# Inputs.net
KiCad netlist of a schematic drawn in Altium Designer
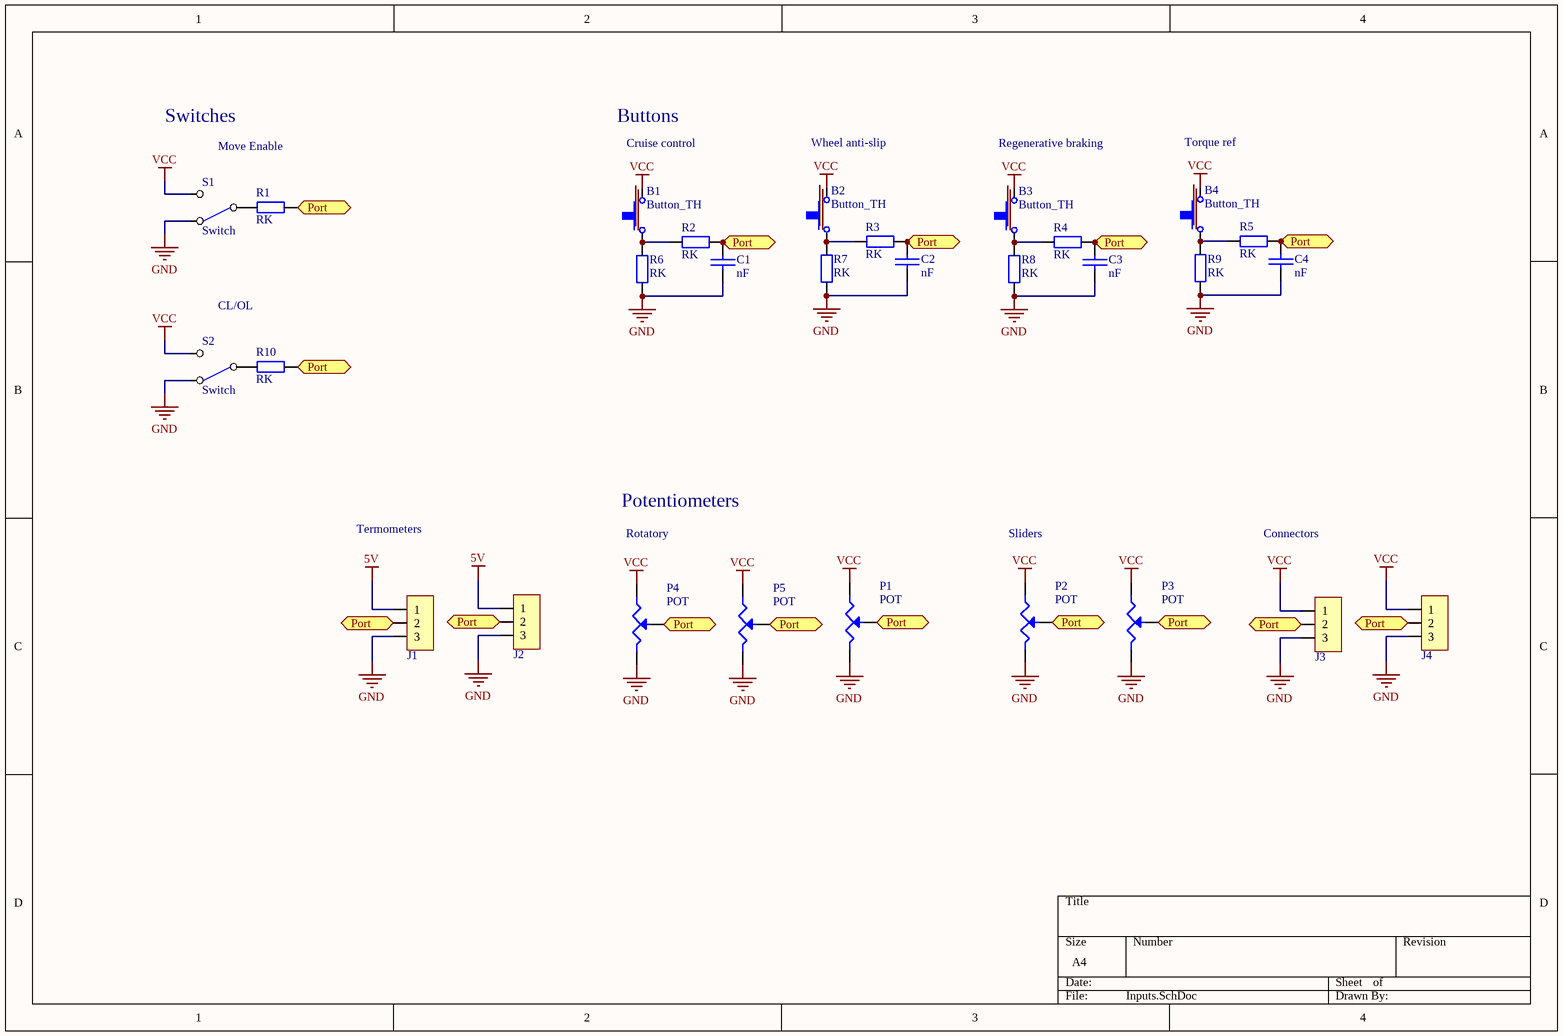
[diagram p0: Inputs.SchDoc]

(export (version "E")
  (design (tool "Eeschema 10.0.6"))
  (components
    (comp (ref "B1")
      (value "Button_TH")
      (footprint "ButtonTH")
      (libsource (lib "SCH_Lib") (part "Button_TH"))
    )
    (comp (ref "B2")
      (value "Button_TH")
      (footprint "ButtonTH")
      (libsource (lib "SCH_Lib") (part "Button_TH"))
    )
    (comp (ref "B3")
      (value "Button_TH")
      (footprint "ButtonTH")
      (libsource (lib "SCH_Lib") (part "Button_TH"))
    )
    (comp (ref "B4")
      (value "Button_TH")
      (footprint "ButtonTH")
      (libsource (lib "SCH_Lib") (part "Button_TH"))
    )
    (comp (ref "C1")
      (value "nF")
      (footprint "1206")
      (description "Condensador")
      (libsource (lib "SCH_Lib") (part "Condensador"))
    )
    (comp (ref "C2")
      (value "nF")
      (footprint "1206")
      (description "Condensador")
      (libsource (lib "SCH_Lib") (part "Condensador"))
    )
    (comp (ref "C3")
      (value "nF")
      (footprint "1206")
      (description "Condensador")
      (libsource (lib "SCH_Lib") (part "Condensador"))
    )
    (comp (ref "C4")
      (value "nF")
      (footprint "1206")
      (description "Condensador")
      (libsource (lib "SCH_Lib") (part "Condensador"))
    )
    (comp (ref "J1")
      (value "Cleva 2 vias")
      (footprint "Con3_KK_256")
      (libsource (lib "SCH_Lib") (part "Con_3"))
    )
    (comp (ref "J2")
      (value "Cleva 2 vias")
      (footprint "Con3_KK_256")
      (libsource (lib "SCH_Lib") (part "Con_3"))
    )
    (comp (ref "J3")
      (value "Cleva 2 vias")
      (footprint "Con3_KK_256")
      (libsource (lib "SCH_Lib") (part "Con_3"))
    )
    (comp (ref "J4")
      (value "Cleva 2 vias")
      (footprint "Con3_KK_256")
      (libsource (lib "SCH_Lib") (part "Con_3"))
    )
    (comp (ref "P1")
      (value "POT")
      (footprint "POT_RK11K1140A3L")
      (description "POTENCIOMETRO")
      (libsource (lib "SCH_Lib") (part "POT"))
    )
    (comp (ref "P2")
      (value "POT")
      (footprint "SliderPot_PTA6044")
      (description "POTENCIOMETRO")
      (libsource (lib "SCH_Lib") (part "POT"))
    )
    (comp (ref "P3")
      (value "POT")
      (footprint "SliderPot_PTA6044")
      (description "POTENCIOMETRO")
      (libsource (lib "SCH_Lib") (part "POT"))
    )
    (comp (ref "P4")
      (value "POT")
      (footprint "POT_RK11K1140A3L")
      (description "POTENCIOMETRO")
      (libsource (lib "SCH_Lib") (part "POT"))
    )
    (comp (ref "P5")
      (value "POT")
      (footprint "POT_RK11K1140A3L")
      (description "POTENCIOMETRO")
      (libsource (lib "SCH_Lib") (part "POT"))
    )
    (comp (ref "R1")
      (value "RK")
      (footprint "1206")
      (description "Resistencia")
      (libsource (lib "SCH_Lib") (part "Resistencia"))
    )
    (comp (ref "R2")
      (value "RK")
      (footprint "1206")
      (description "Resistencia")
      (libsource (lib "SCH_Lib") (part "Resistencia"))
    )
    (comp (ref "R3")
      (value "RK")
      (footprint "1206")
      (description "Resistencia")
      (libsource (lib "SCH_Lib") (part "Resistencia"))
    )
    (comp (ref "R4")
      (value "RK")
      (footprint "1206")
      (description "Resistencia")
      (libsource (lib "SCH_Lib") (part "Resistencia"))
    )
    (comp (ref "R5")
      (value "RK")
      (footprint "1206")
      (description "Resistencia")
      (libsource (lib "SCH_Lib") (part "Resistencia"))
    )
    (comp (ref "R6")
      (value "RK")
      (footprint "1206")
      (description "Resistencia")
      (libsource (lib "SCH_Lib") (part "Resistencia"))
    )
    (comp (ref "R7")
      (value "RK")
      (footprint "1206")
      (description "Resistencia")
      (libsource (lib "SCH_Lib") (part "Resistencia"))
    )
    (comp (ref "R8")
      (value "RK")
      (footprint "1206")
      (description "Resistencia")
      (libsource (lib "SCH_Lib") (part "Resistencia"))
    )
    (comp (ref "R9")
      (value "RK")
      (footprint "1206")
      (description "Resistencia")
      (libsource (lib "SCH_Lib") (part "Resistencia"))
    )
    (comp (ref "R10")
      (value "RK")
      (footprint "1206")
      (description "Resistencia")
      (libsource (lib "SCH_Lib") (part "Resistencia"))
    )
    (comp (ref "S1") (value "Switch") (footprint "SwitchTH_2Pos") (libsource (lib "SCH_Lib") (part "Switch")))
    (comp (ref "S2") (value "Switch") (footprint "SwitchTH_2Pos") (libsource (lib "SCH_Lib") (part "Switch")))
  )
  (nets
    (net (code "1") (name "/Port") (class "Default")
      (node (ref "C1") (pin "1") (pintype "passive"))
      (node (ref "C2") (pin "1") (pintype "passive"))
      (node (ref "C3") (pin "1") (pintype "passive"))
      (node (ref "C4") (pin "1") (pintype "passive"))
      (node (ref "J1") (pin "2") (pinfunction "2_2") (pintype "passive"))
      (node (ref "J2") (pin "2") (pinfunction "2_2") (pintype "passive"))
      (node (ref "J3") (pin "2") (pinfunction "2_2") (pintype "passive"))
      (node (ref "J4") (pin "2") (pinfunction "2_2") (pintype "passive"))
      (node (ref "P1") (pin "2") (pinfunction "2_2") (pintype "passive"))
      (node (ref "P2") (pin "2") (pinfunction "2_2") (pintype "passive"))
      (node (ref "P3") (pin "2") (pinfunction "2_2") (pintype "passive"))
      (node (ref "P4") (pin "2") (pinfunction "2_2") (pintype "passive"))
      (node (ref "P5") (pin "2") (pinfunction "2_2") (pintype "passive"))
      (node (ref "R1") (pin "2") (pinfunction "2_2") (pintype "passive"))
      (node (ref "R10") (pin "2") (pinfunction "2_2") (pintype "passive"))
      (node (ref "R2") (pin "1") (pinfunction "1_1") (pintype "passive"))
      (node (ref "R3") (pin "1") (pinfunction "1_1") (pintype "passive"))
      (node (ref "R4") (pin "1") (pinfunction "1_1") (pintype "passive"))
      (node (ref "R5") (pin "1") (pinfunction "1_1") (pintype "passive"))
    )
    (net (code "2") (name "5V") (class "Default")
      (node (ref "J1") (pin "1") (pinfunction "1_1") (pintype "passive"))
      (node (ref "J2") (pin "1") (pinfunction "1_1") (pintype "passive"))
    )
    (net (code "3") (name "GND") (class "Default")
      (node (ref "C1") (pin "2") (pintype "passive"))
      (node (ref "C2") (pin "2") (pintype "passive"))
      (node (ref "C3") (pin "2") (pintype "passive"))
      (node (ref "C4") (pin "2") (pintype "passive"))
      (node (ref "J1") (pin "3") (pinfunction "3_3") (pintype "passive"))
      (node (ref "J2") (pin "3") (pinfunction "3_3") (pintype "passive"))
      (node (ref "J3") (pin "3") (pinfunction "3_3") (pintype "passive"))
      (node (ref "J4") (pin "3") (pinfunction "3_3") (pintype "passive"))
      (node (ref "P1") (pin "3") (pinfunction "3_3") (pintype "passive"))
      (node (ref "P2") (pin "3") (pinfunction "3_3") (pintype "passive"))
      (node (ref "P3") (pin "3") (pinfunction "3_3") (pintype "passive"))
      (node (ref "P4") (pin "3") (pinfunction "3_3") (pintype "passive"))
      (node (ref "P5") (pin "3") (pinfunction "3_3") (pintype "passive"))
      (node (ref "R6") (pin "2") (pinfunction "2_2") (pintype "passive"))
      (node (ref "R7") (pin "2") (pinfunction "2_2") (pintype "passive"))
      (node (ref "R8") (pin "2") (pinfunction "2_2") (pintype "passive"))
      (node (ref "R9") (pin "2") (pinfunction "2_2") (pintype "passive"))
      (node (ref "S1") (pin "0") (pinfunction "ON1_0") (pintype "passive"))
      (node (ref "S2") (pin "0") (pinfunction "ON1_0") (pintype "passive"))
    )
    (net (code "4") (name "Net-(B1-Pad1)") (class "Default")
      (node (ref "B1") (pin "1") (pinfunction "1_1") (pintype "passive"))
      (node (ref "R2") (pin "2") (pinfunction "2_2") (pintype "passive"))
      (node (ref "R6") (pin "1") (pinfunction "1_1") (pintype "passive"))
    )
    (net (code "5") (name "Net-(B2-Pad1)") (class "Default")
      (node (ref "B2") (pin "1") (pinfunction "1_1") (pintype "passive"))
      (node (ref "R3") (pin "2") (pinfunction "2_2") (pintype "passive"))
      (node (ref "R7") (pin "1") (pinfunction "1_1") (pintype "passive"))
    )
    (net (code "6") (name "Net-(B3-Pad1)") (class "Default")
      (node (ref "B3") (pin "1") (pinfunction "1_1") (pintype "passive"))
      (node (ref "R4") (pin "2") (pinfunction "2_2") (pintype "passive"))
      (node (ref "R8") (pin "1") (pinfunction "1_1") (pintype "passive"))
    )
    (net (code "7") (name "Net-(B4-Pad1)") (class "Default")
      (node (ref "B4") (pin "1") (pinfunction "1_1") (pintype "passive"))
      (node (ref "R5") (pin "2") (pinfunction "2_2") (pintype "passive"))
      (node (ref "R9") (pin "1") (pinfunction "1_1") (pintype "passive"))
    )
    (net (code "8") (name "Net-(S1-COMMON)") (class "Default")
      (node (ref "R1") (pin "1") (pinfunction "1_1") (pintype "passive"))
      (node (ref "S1") (pin "1") (pinfunction "COMMON_1") (pintype "passive"))
    )
    (net (code "9") (name "Net-(S2-COMMON)") (class "Default")
      (node (ref "R10") (pin "1") (pinfunction "1_1") (pintype "passive"))
      (node (ref "S2") (pin "1") (pinfunction "COMMON_1") (pintype "passive"))
    )
    (net (code "10") (name "VCC") (class "Default")
      (node (ref "B1") (pin "0") (pinfunction "0_0") (pintype "passive"))
      (node (ref "B2") (pin "0") (pinfunction "0_0") (pintype "passive"))
      (node (ref "B3") (pin "0") (pinfunction "0_0") (pintype "passive"))
      (node (ref "B4") (pin "0") (pinfunction "0_0") (pintype "passive"))
      (node (ref "J3") (pin "1") (pinfunction "1_1") (pintype "passive"))
      (node (ref "J4") (pin "1") (pinfunction "1_1") (pintype "passive"))
      (node (ref "P1") (pin "1") (pinfunction "1_1") (pintype "passive"))
      (node (ref "P2") (pin "1") (pinfunction "1_1") (pintype "passive"))
      (node (ref "P3") (pin "1") (pinfunction "1_1") (pintype "passive"))
      (node (ref "P4") (pin "1") (pinfunction "1_1") (pintype "passive"))
      (node (ref "P5") (pin "1") (pinfunction "1_1") (pintype "passive"))
      (node (ref "S1") (pin "2") (pinfunction "ON2_2") (pintype "passive"))
      (node (ref "S2") (pin "2") (pinfunction "ON2_2") (pintype "passive"))
    )
  )
)
